# OPA4134_Headphones.net
KiCad netlist of a schematic drawn in EAGLE
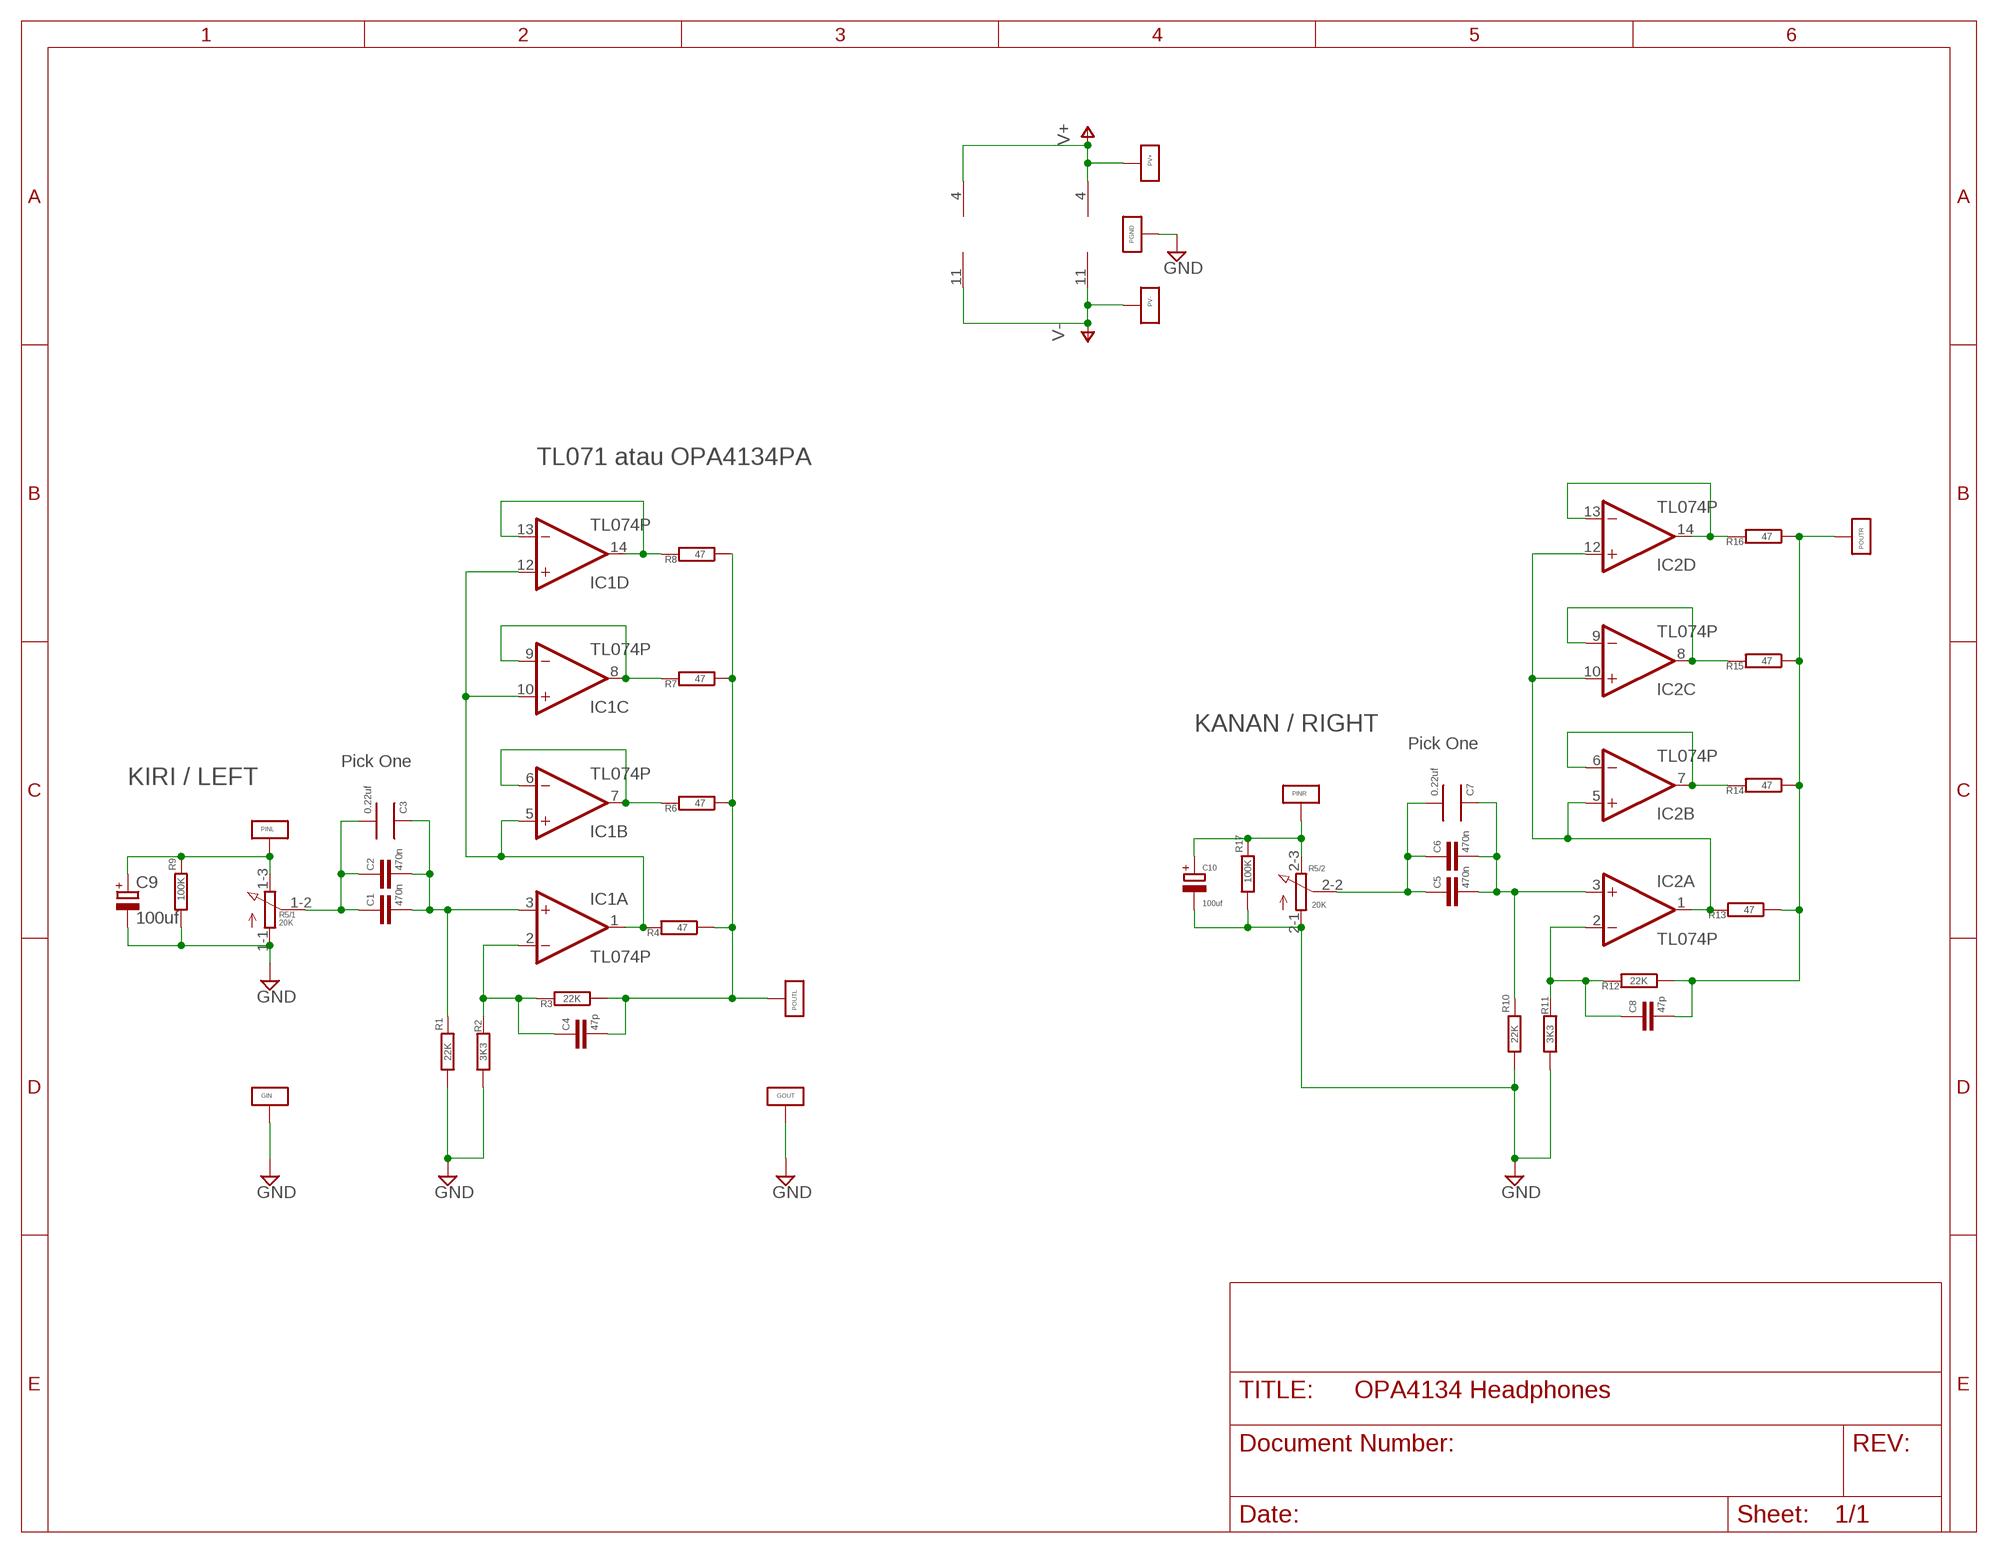
[diagram p0: schematic, sheet 1]

(export (version "E")
  (design (tool "Eeschema 10.0.6"))
  (components
    (comp (ref "C1")
      (value "470n")
      (footprint "eagle-import:C050-025X075")
      (libsource (lib "eagle-import") (part "C-EU050-025X075"))
    )
    (comp (ref "C2")
      (value "470n")
      (footprint "eagle-import:C102-054X133")
      (libsource (lib "eagle-import") (part "C-EU102-054X133"))
    )
    (comp (ref "C3")
      (value "0.22uf")
      (footprint "eagle-import:BENICCAP")
      (libsource (lib "eagle-import") (part "BENICCAPBENIC-SMALL"))
    )
    (comp (ref "C4")
      (value "47p")
      (footprint "eagle-import:C050-025X075")
      (libsource (lib "eagle-import") (part "C-EU050-025X075"))
    )
    (comp (ref "C5")
      (value "470n")
      (footprint "eagle-import:C050-025X075")
      (libsource (lib "eagle-import") (part "C-EU050-025X075"))
    )
    (comp (ref "C6")
      (value "470n")
      (footprint "eagle-import:C102-054X133")
      (libsource (lib "eagle-import") (part "C-EU102-054X133"))
    )
    (comp (ref "C7")
      (value "0.22uf")
      (footprint "eagle-import:BENICCAP")
      (libsource (lib "eagle-import") (part "BENICCAPBENIC-SMALL"))
    )
    (comp (ref "C8")
      (value "47p")
      (footprint "eagle-import:C050-025X075")
      (libsource (lib "eagle-import") (part "C-EU050-025X075"))
    )
    (comp (ref "C9")
      (value "100uf")
      (footprint "eagle-import:E2,5-7")
      (libsource (lib "eagle-import") (part "CPOL-EUE2.5-7"))
    )
    (comp (ref "C10")
      (value "100uf")
      (footprint "eagle-import:E2,5-7")
      (libsource (lib "eagle-import") (part "CPOL-EUE2.5-7"))
    )
    (comp (ref "GIN")
      (value "PIN-BIG1X")
      (footprint "eagle-import:PIN-BIG")
      (libsource (lib "eagle-import") (part "PIN-BIG1X"))
    )
    (comp (ref "GOUT")
      (value "PIN-BIG1X")
      (footprint "eagle-import:PIN-BIG")
      (libsource (lib "eagle-import") (part "PIN-BIG1X"))
    )
    (comp (ref "IC1")
      (value "TL074P")
      (footprint "eagle-import:DIL14")
      (libsource (lib "eagle-import") (part "TL074P"))
    )
    (comp (ref "IC2")
      (value "TL074P")
      (footprint "eagle-import:DIL14")
      (libsource (lib "eagle-import") (part "TL074P"))
    )
    (comp (ref "PGND")
      (value "PIN-BIG1X")
      (footprint "eagle-import:PIN-BIG")
      (libsource (lib "eagle-import") (part "PIN-BIG1X"))
    )
    (comp (ref "PINL")
      (value "PIN-BIG1X")
      (footprint "eagle-import:PIN-BIG")
      (libsource (lib "eagle-import") (part "PIN-BIG1X"))
    )
    (comp (ref "PINR")
      (value "PIN-BIG1X")
      (footprint "eagle-import:PIN-BIG")
      (libsource (lib "eagle-import") (part "PIN-BIG1X"))
    )
    (comp (ref "POUTL")
      (value "PIN-BIG1X")
      (footprint "eagle-import:PIN-BIG")
      (libsource (lib "eagle-import") (part "PIN-BIG1X"))
    )
    (comp (ref "POUTR")
      (value "PIN-BIG1X")
      (footprint "eagle-import:PIN-BIG")
      (libsource (lib "eagle-import") (part "PIN-BIG1X"))
    )
    (comp (ref "PV+")
      (value "PIN-BIG1X")
      (footprint "eagle-import:PIN-BIG")
      (libsource (lib "eagle-import") (part "PIN-BIG1X"))
    )
    (comp (ref "PV-")
      (value "PIN-BIG1X")
      (footprint "eagle-import:PIN-BIG")
      (libsource (lib "eagle-import") (part "PIN-BIG1X"))
    )
    (comp (ref "R1")
      (value "22K")
      (footprint "eagle-import:0204_7")
      (libsource (lib "eagle-import") (part "R-EU_0204/7"))
    )
    (comp (ref "R2")
      (value "3K3")
      (footprint "eagle-import:0204_7")
      (libsource (lib "eagle-import") (part "R-EU_0204/7"))
    )
    (comp (ref "R3")
      (value "22K")
      (footprint "eagle-import:0204_7")
      (libsource (lib "eagle-import") (part "R-EU_0204/7"))
    )
    (comp (ref "R4")
      (value "47")
      (footprint "eagle-import:0204_7")
      (libsource (lib "eagle-import") (part "R-EU_0204/7"))
    )
    (comp (ref "R5")
      (value "20K")
      (footprint "eagle-import:3RP_1610G")
      (libsource (lib "eagle-import") (part "3RP/1610G"))
    )
    (comp (ref "R6")
      (value "47")
      (footprint "eagle-import:0204_7")
      (libsource (lib "eagle-import") (part "R-EU_0204/7"))
    )
    (comp (ref "R7")
      (value "47")
      (footprint "eagle-import:0204_7")
      (libsource (lib "eagle-import") (part "R-EU_0204/7"))
    )
    (comp (ref "R8")
      (value "47")
      (footprint "eagle-import:0204_7")
      (libsource (lib "eagle-import") (part "R-EU_0204/7"))
    )
    (comp (ref "R9")
      (value "100K")
      (footprint "eagle-import:0204_7")
      (libsource (lib "eagle-import") (part "R-EU_0204/7"))
    )
    (comp (ref "R10")
      (value "22K")
      (footprint "eagle-import:0204_7")
      (libsource (lib "eagle-import") (part "R-EU_0204/7"))
    )
    (comp (ref "R11")
      (value "3K3")
      (footprint "eagle-import:0204_7")
      (libsource (lib "eagle-import") (part "R-EU_0204/7"))
    )
    (comp (ref "R12")
      (value "22K")
      (footprint "eagle-import:0204_7")
      (libsource (lib "eagle-import") (part "R-EU_0204/7"))
    )
    (comp (ref "R13")
      (value "47")
      (footprint "eagle-import:0204_7")
      (libsource (lib "eagle-import") (part "R-EU_0204/7"))
    )
    (comp (ref "R14")
      (value "47")
      (footprint "eagle-import:0204_7")
      (libsource (lib "eagle-import") (part "R-EU_0204/7"))
    )
    (comp (ref "R15")
      (value "47")
      (footprint "eagle-import:0204_7")
      (libsource (lib "eagle-import") (part "R-EU_0204/7"))
    )
    (comp (ref "R16")
      (value "47")
      (footprint "eagle-import:0204_7")
      (libsource (lib "eagle-import") (part "R-EU_0204/7"))
    )
    (comp (ref "R17")
      (value "100K")
      (footprint "eagle-import:0204_7")
      (libsource (lib "eagle-import") (part "R-EU_0204/7"))
    )
  )
  (nets
    (net (code "1") (name "GND") (class "Default")
      (node (ref "C10") (pin "-") (pinfunction "-_-") (pintype "passive"))
      (node (ref "C9") (pin "-") (pinfunction "-_-") (pintype "passive"))
      (node (ref "GIN") (pin "P$1") (pinfunction "P$1_P$1") (pintype "bidirectional"))
      (node (ref "GOUT") (pin "P$1") (pinfunction "P$1_P$1") (pintype "bidirectional"))
      (node (ref "PGND") (pin "P$1") (pinfunction "P$1_P$1") (pintype "bidirectional"))
      (node (ref "R1") (pin "1") (pinfunction "1_1") (pintype "passive"))
      (node (ref "R10") (pin "1") (pinfunction "1_1") (pintype "passive"))
      (node (ref "R11") (pin "1") (pinfunction "1_1") (pintype "passive"))
      (node (ref "R17") (pin "1") (pinfunction "1_1") (pintype "passive"))
      (node (ref "R2") (pin "1") (pinfunction "1_1") (pintype "passive"))
      (node (ref "R5") (pin "1-1") (pinfunction "A_1-1") (pintype "passive"))
      (node (ref "R5") (pin "2-1") (pinfunction "A_2-1") (pintype "passive"))
      (node (ref "R9") (pin "1") (pinfunction "1_1") (pintype "passive"))
    )
    (net (code "2") (name "Net-(C4-Pad2)") (class "Default")
      (node (ref "C4") (pin "2") (pinfunction "2_2") (pintype "passive"))
      (node (ref "POUTL") (pin "P$1") (pinfunction "P$1_P$1") (pintype "bidirectional"))
      (node (ref "R3") (pin "1") (pinfunction "1_1") (pintype "passive"))
      (node (ref "R4") (pin "1") (pinfunction "1_1") (pintype "passive"))
      (node (ref "R6") (pin "1") (pinfunction "1_1") (pintype "passive"))
      (node (ref "R7") (pin "1") (pinfunction "1_1") (pintype "passive"))
      (node (ref "R8") (pin "1") (pinfunction "1_1") (pintype "passive"))
    )
    (net (code "3") (name "Net-(C8-Pad2)") (class "Default")
      (node (ref "C8") (pin "2") (pinfunction "2_2") (pintype "passive"))
      (node (ref "POUTR") (pin "P$1") (pinfunction "P$1_P$1") (pintype "bidirectional"))
      (node (ref "R12") (pin "1") (pinfunction "1_1") (pintype "passive"))
      (node (ref "R13") (pin "1") (pinfunction "1_1") (pintype "passive"))
      (node (ref "R14") (pin "1") (pinfunction "1_1") (pintype "passive"))
      (node (ref "R15") (pin "1") (pinfunction "1_1") (pintype "passive"))
      (node (ref "R16") (pin "1") (pinfunction "1_1") (pintype "passive"))
    )
    (net (code "4") (name "Net-(IC1A-+IN)") (class "Default")
      (node (ref "C1") (pin "2") (pinfunction "2_2") (pintype "passive"))
      (node (ref "C2") (pin "2") (pinfunction "2_2") (pintype "passive"))
      (node (ref "C3") (pin "PIN2") (pinfunction "PIN2_PIN2") (pintype "bidirectional"))
      (node (ref "IC1") (pin "3") (pinfunction "+IN_3") (pintype "input"))
      (node (ref "R1") (pin "2") (pinfunction "2_2") (pintype "passive"))
    )
    (net (code "5") (name "Net-(IC1A--IN)") (class "Default")
      (node (ref "C4") (pin "1") (pinfunction "1_1") (pintype "passive"))
      (node (ref "IC1") (pin "2") (pinfunction "-IN_2") (pintype "input"))
      (node (ref "R2") (pin "2") (pinfunction "2_2") (pintype "passive"))
      (node (ref "R3") (pin "2") (pinfunction "2_2") (pintype "passive"))
    )
    (net (code "6") (name "Net-(IC1A-OUT)") (class "Default")
      (node (ref "IC1") (pin "1") (pinfunction "OUT_1") (pintype "output"))
      (node (ref "IC1") (pin "10") (pinfunction "+IN_10") (pintype "input"))
      (node (ref "IC1") (pin "12") (pinfunction "+IN_12") (pintype "input"))
      (node (ref "IC1") (pin "5") (pinfunction "+IN_5") (pintype "input"))
      (node (ref "R4") (pin "2") (pinfunction "2_2") (pintype "passive"))
    )
    (net (code "7") (name "Net-(IC1B--IN)") (class "Default")
      (node (ref "IC1") (pin "6") (pinfunction "-IN_6") (pintype "input"))
      (node (ref "IC1") (pin "7") (pinfunction "OUT_7") (pintype "output"))
      (node (ref "R6") (pin "2") (pinfunction "2_2") (pintype "passive"))
    )
    (net (code "8") (name "Net-(IC1C--IN)") (class "Default")
      (node (ref "IC1") (pin "8") (pinfunction "OUT_8") (pintype "output"))
      (node (ref "IC1") (pin "9") (pinfunction "-IN_9") (pintype "input"))
      (node (ref "R7") (pin "2") (pinfunction "2_2") (pintype "passive"))
    )
    (net (code "9") (name "Net-(IC1D--IN)") (class "Default")
      (node (ref "IC1") (pin "13") (pinfunction "-IN_13") (pintype "input"))
      (node (ref "IC1") (pin "14") (pinfunction "OUT_14") (pintype "output"))
      (node (ref "R8") (pin "2") (pinfunction "2_2") (pintype "passive"))
    )
    (net (code "10") (name "Net-(IC2A-+IN)") (class "Default")
      (node (ref "C5") (pin "2") (pinfunction "2_2") (pintype "passive"))
      (node (ref "C6") (pin "2") (pinfunction "2_2") (pintype "passive"))
      (node (ref "C7") (pin "PIN2") (pinfunction "PIN2_PIN2") (pintype "bidirectional"))
      (node (ref "IC2") (pin "3") (pinfunction "+IN_3") (pintype "input"))
      (node (ref "R10") (pin "2") (pinfunction "2_2") (pintype "passive"))
    )
    (net (code "11") (name "Net-(IC2A--IN)") (class "Default")
      (node (ref "C8") (pin "1") (pinfunction "1_1") (pintype "passive"))
      (node (ref "IC2") (pin "2") (pinfunction "-IN_2") (pintype "input"))
      (node (ref "R11") (pin "2") (pinfunction "2_2") (pintype "passive"))
      (node (ref "R12") (pin "2") (pinfunction "2_2") (pintype "passive"))
    )
    (net (code "12") (name "Net-(IC2A-OUT)") (class "Default")
      (node (ref "IC2") (pin "1") (pinfunction "OUT_1") (pintype "output"))
      (node (ref "IC2") (pin "10") (pinfunction "+IN_10") (pintype "input"))
      (node (ref "IC2") (pin "12") (pinfunction "+IN_12") (pintype "input"))
      (node (ref "IC2") (pin "5") (pinfunction "+IN_5") (pintype "input"))
      (node (ref "R13") (pin "2") (pinfunction "2_2") (pintype "passive"))
    )
    (net (code "13") (name "Net-(IC2B--IN)") (class "Default")
      (node (ref "IC2") (pin "6") (pinfunction "-IN_6") (pintype "input"))
      (node (ref "IC2") (pin "7") (pinfunction "OUT_7") (pintype "output"))
      (node (ref "R14") (pin "2") (pinfunction "2_2") (pintype "passive"))
    )
    (net (code "14") (name "Net-(IC2C--IN)") (class "Default")
      (node (ref "IC2") (pin "8") (pinfunction "OUT_8") (pintype "output"))
      (node (ref "IC2") (pin "9") (pinfunction "-IN_9") (pintype "input"))
      (node (ref "R15") (pin "2") (pinfunction "2_2") (pintype "passive"))
    )
    (net (code "15") (name "Net-(IC2D--IN)") (class "Default")
      (node (ref "IC2") (pin "13") (pinfunction "-IN_13") (pintype "input"))
      (node (ref "IC2") (pin "14") (pinfunction "OUT_14") (pintype "output"))
      (node (ref "R16") (pin "2") (pinfunction "2_2") (pintype "passive"))
    )
    (net (code "16") (name "Net-(R5A-E)") (class "Default")
      (node (ref "C9") (pin "+") (pinfunction "+_+") (pintype "passive"))
      (node (ref "PINL") (pin "P$1") (pinfunction "P$1_P$1") (pintype "bidirectional"))
      (node (ref "R5") (pin "1-3") (pinfunction "E_1-3") (pintype "passive"))
      (node (ref "R9") (pin "2") (pinfunction "2_2") (pintype "passive"))
    )
    (net (code "17") (name "Net-(R5A-S)") (class "Default")
      (node (ref "C1") (pin "1") (pinfunction "1_1") (pintype "passive"))
      (node (ref "C2") (pin "1") (pinfunction "1_1") (pintype "passive"))
      (node (ref "C3") (pin "PIN1") (pinfunction "PIN1_PIN1") (pintype "bidirectional"))
      (node (ref "R5") (pin "1-2") (pinfunction "S_1-2") (pintype "passive"))
    )
    (net (code "18") (name "Net-(R5B-E)") (class "Default")
      (node (ref "C10") (pin "+") (pinfunction "+_+") (pintype "passive"))
      (node (ref "PINR") (pin "P$1") (pinfunction "P$1_P$1") (pintype "bidirectional"))
      (node (ref "R17") (pin "2") (pinfunction "2_2") (pintype "passive"))
      (node (ref "R5") (pin "2-3") (pinfunction "E_2-3") (pintype "passive"))
    )
    (net (code "19") (name "Net-(R5B-S)") (class "Default")
      (node (ref "C5") (pin "1") (pinfunction "1_1") (pintype "passive"))
      (node (ref "C6") (pin "1") (pinfunction "1_1") (pintype "passive"))
      (node (ref "C7") (pin "PIN1") (pinfunction "PIN1_PIN1") (pintype "bidirectional"))
      (node (ref "R5") (pin "2-2") (pinfunction "S_2-2") (pintype "passive"))
    )
    (net (code "20") (name "V+") (class "Default")
      (node (ref "IC1") (pin "4") (pinfunction "V+_4") (pintype "power_in"))
      (node (ref "IC2") (pin "4") (pinfunction "V+_4") (pintype "power_in"))
      (node (ref "PV+") (pin "P$1") (pinfunction "P$1_P$1") (pintype "bidirectional"))
    )
    (net (code "21") (name "V-") (class "Default")
      (node (ref "IC1") (pin "11") (pinfunction "V-_11") (pintype "power_in"))
      (node (ref "IC2") (pin "11") (pinfunction "V-_11") (pintype "power_in"))
      (node (ref "PV-") (pin "P$1") (pinfunction "P$1_P$1") (pintype "bidirectional"))
    )
  )
)
